# Crystal_oscillator.net
KiCad netlist of a schematic drawn in Altium Designer
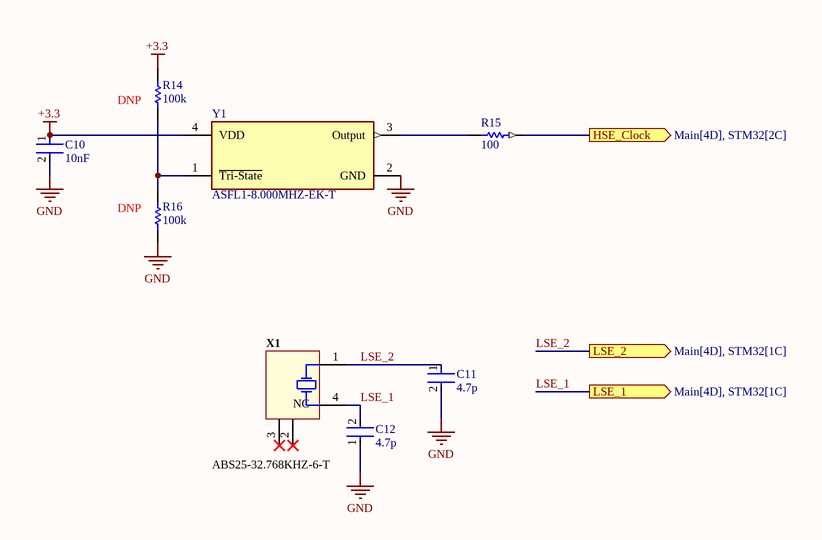
[diagram p0: Crystal_oscillator.SchDoc]

(export (version "E")
  (design (tool "Eeschema 10.0.6"))
  (components
    (comp (ref "C10")
      (value "10nF")
      (footprint "FP-0805-L_2_01_0_2-W_1_25-IPC_B")
      (description "General Purpose Ceramic Capacitor, 0805, 10nF, 10%, X7R, 15%, 100V")
      (fields (field (name "VOLTAGE") "100V") (field (name "TOLERANCE") "10%"))
      (libsource (lib "Altium Content Vault") (part "b4654b650e69147ec39a6b967a45e02"))
    )
    (comp (ref "C11")
      (value "4.7p")
      (footprint "FP-C0603C-CF-MFG")
      (description "CAP CER 0.1UF 50V X7R 0603")
      (fields (field (name "TOLERANCE") "0.1") (field (name "MANUFACTURER") "KEMET"))
      (libsource (lib "Altium Content Vault") (part "b4654b650e69147ec39a6b967a45e02"))
    )
    (comp (ref "C12")
      (value "4.7p")
      (footprint "FP-C0603C-CF-MFG")
      (description "CAP CER 0.1UF 50V X7R 0603")
      (fields (field (name "TOLERANCE") "0.1") (field (name "MANUFACTURER") "KEMET"))
      (libsource (lib "Altium Content Vault") (part "b4654b650e69147ec39a6b967a45e02"))
    )
    (comp (ref "R14")
      (value "100k")
      (footprint "RESC2013X50X30LL20T20")
      (fields (field (name "MANUFACTURER") "Vishay Dale") (field (name "PART NUMBER") "CRCW08050000Z0EA"))
      (libsource (lib "Altium Content Vault") (part "RES"))
    )
    (comp (ref "R15")
      (value "100")
      (footprint "RESC2013X50X30LL20T20")
      (fields (field (name "MANUFACTURER") "Vishay Dale") (field (name "PART NUMBER") "CRCW08050000Z0EA"))
      (libsource (lib "") (part "RES_1"))
    )
    (comp (ref "R16")
      (value "100k")
      (footprint "RESC2013X50X30LL20T20")
      (fields (field (name "MANUFACTURER") "Vishay Dale") (field (name "PART NUMBER") "CRCW08050000Z0EA"))
      (libsource (lib "Altium Content Vault") (part "RES"))
    )
    (comp (ref "X1")
      (value "ABS25-32.768KHZ-6-T")
      (footprint "ABRA-ABS25-4_V")
      (fields (field (name "TOLERANCE") "20PPM") (field (name "MANUFACTURER") "Abracon"))
      (libsource (lib "Altium Content Vault") (part "ABRA-XTAL_1-4-4"))
    )
    (comp (ref "Y1")
      (value "ASFL1-8.000MHZ-EK-T")
      (footprint "FP-ASFL1-MFG")
      (description "XTAL Oscillator 8MHz ±30ppm HCMOS, TTL 3.3V 4-SMD 5mm x 3.2mm")
      (libsource (lib "Altium Content Vault") (part "47df00dc2349451232cb22fac08fbff"))
    )
  )
  (nets
    (net (code "1") (name "+3.3") (class "Default")
      (node (ref "C10") (pin "1") (pinfunction "1_1") (pintype "passive"))
      (node (ref "R14") (pin "2") (pinfunction "2_2") (pintype "passive"))
      (node (ref "Y1") (pin "4") (pinfunction "VDD_4") (pintype "power_in"))
    )
    (net (code "2") (name "/HSE_Clock") (class "Default")
      (node (ref "R15") (pin "2") (pinfunction "2_2") (pintype "output"))
    )
    (net (code "3") (name "/LSE_1") (class "Default")
      (node (ref "C12") (pin "2") (pinfunction "2_2") (pintype "passive"))
      (node (ref "X1") (pin "4") (pinfunction "X2_4") (pintype "passive"))
    )
    (net (code "4") (name "/LSE_2") (class "Default")
      (node (ref "C11") (pin "1") (pinfunction "1_1") (pintype "passive"))
      (node (ref "X1") (pin "1") (pinfunction "X1_1") (pintype "passive"))
    )
    (net (code "5") (name "GND") (class "Default")
      (node (ref "C10") (pin "2") (pinfunction "2_2") (pintype "passive"))
      (node (ref "C11") (pin "2") (pinfunction "2_2") (pintype "passive"))
      (node (ref "C12") (pin "1") (pinfunction "1_1") (pintype "passive"))
      (node (ref "R16") (pin "1") (pinfunction "1_1") (pintype "passive"))
      (node (ref "Y1") (pin "2") (pinfunction "GND_2") (pintype "power_in"))
    )
    (net (code "6") (name "Net-(Y1-Output)") (class "Default")
      (node (ref "R15") (pin "1") (pinfunction "1_1") (pintype "passive"))
      (node (ref "Y1") (pin "3") (pinfunction "Output_3") (pintype "output"))
    )
    (net (code "7") (name "Net-(Y1-~{Tri-State})") (class "Default")
      (node (ref "R14") (pin "1") (pinfunction "1_1") (pintype "passive"))
      (node (ref "R16") (pin "2") (pinfunction "2_2") (pintype "passive"))
      (node (ref "Y1") (pin "1") (pinfunction "~{Tri-State}_1") (pintype "passive"))
    )
    (net (code "8") (name "unconnected-(X1-NC-Pad2)") (class "Default")
      (node (ref "X1") (pin "2") (pinfunction "NC_2") (pintype "passive+no_connect"))
    )
    (net (code "9") (name "unconnected-(X1-NC-Pad3)") (class "Default")
      (node (ref "X1") (pin "3") (pinfunction "NC_3") (pintype "passive+no_connect"))
    )
  )
)
